# mcu.net
KiCad netlist of a schematic drawn in Altium Designer
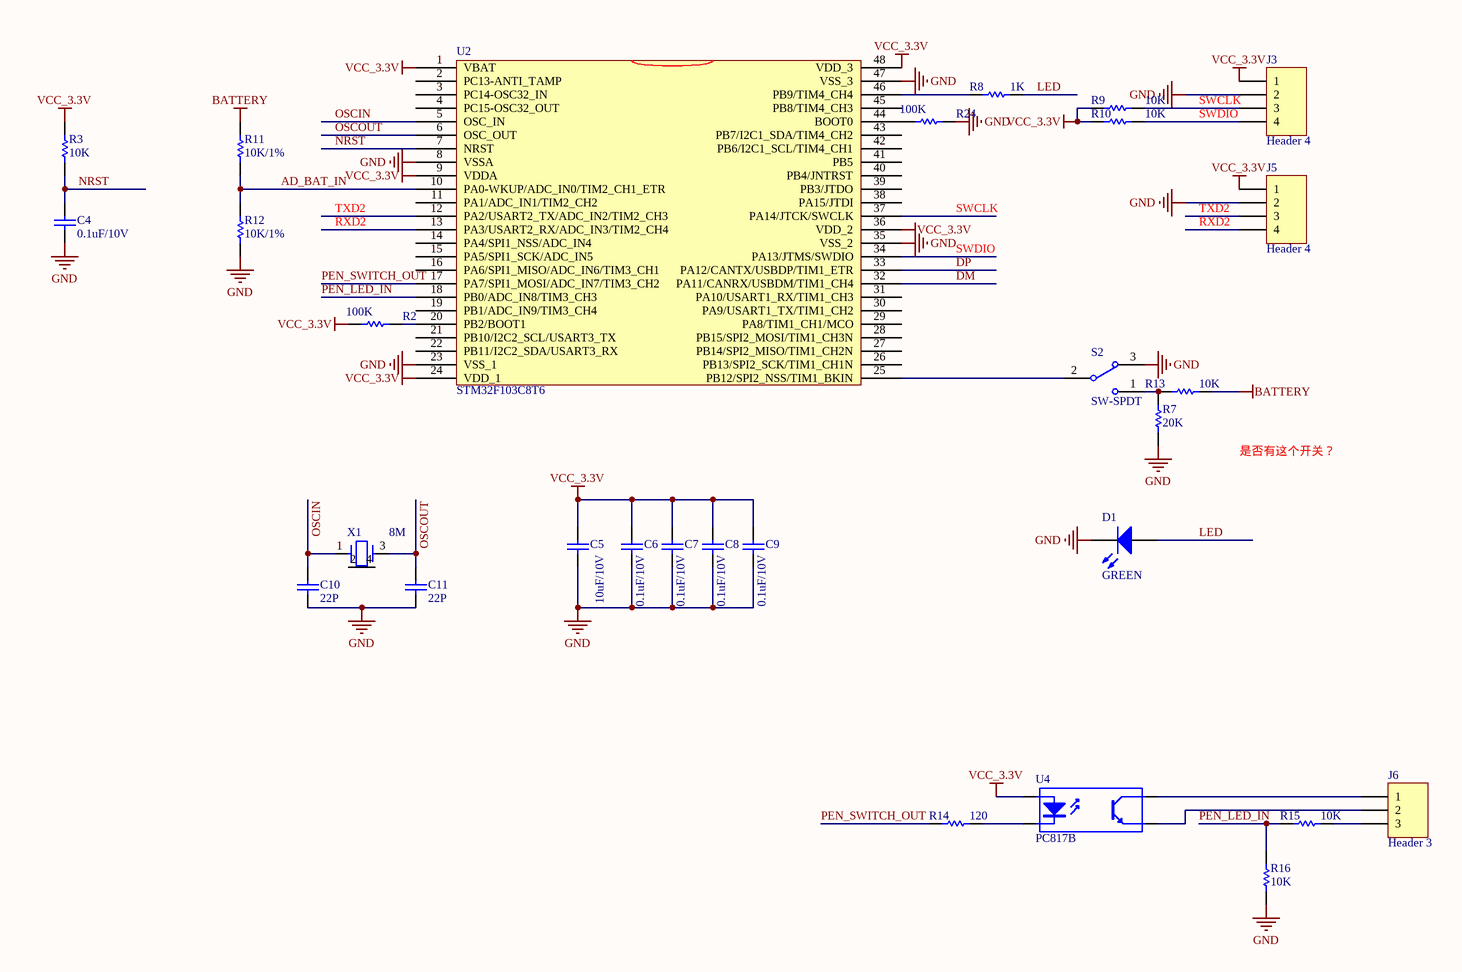
[diagram p0: mcu.SchDoc]

(export (version "E")
  (design (tool "Eeschema 10.0.6"))
  (components
    (comp (ref "C4")
      (value "0.1uF/10V")
      (footprint "0402C")
      (description "Capacitor")
      (fields (field (name "PUBLISHER") "Altium Limited"))
      (libsource (lib "Miscellaneous Devices") (part "Cap"))
    )
    (comp (ref "C5")
      (value "10uF/10V")
      (footprint "0603C")
      (description "Capacitor")
      (fields (field (name "PUBLISHER") "Altium Limited"))
      (libsource (lib "Miscellaneous Devices") (part "Cap"))
    )
    (comp (ref "C6")
      (value "0.1uF/10V")
      (footprint "0402C")
      (description "Capacitor")
      (fields (field (name "PUBLISHER") "Altium Limited"))
      (libsource (lib "Miscellaneous Devices") (part "Cap"))
    )
    (comp (ref "C7")
      (value "0.1uF/10V")
      (footprint "0402C")
      (description "Capacitor")
      (fields (field (name "PUBLISHER") "Altium Limited"))
      (libsource (lib "Miscellaneous Devices") (part "Cap"))
    )
    (comp (ref "C8")
      (value "0.1uF/10V")
      (footprint "0402C")
      (description "Capacitor")
      (fields (field (name "PUBLISHER") "Altium Limited"))
      (libsource (lib "Miscellaneous Devices") (part "Cap"))
    )
    (comp (ref "C9")
      (value "0.1uF/10V")
      (footprint "0402C")
      (description "Capacitor")
      (fields (field (name "PUBLISHER") "Altium Limited"))
      (libsource (lib "Miscellaneous Devices") (part "Cap"))
    )
    (comp (ref "C10")
      (value "22P")
      (footprint "0402C")
      (description "Capacitor")
      (fields (field (name "PUBLISHER") "Altium Limited"))
      (libsource (lib "Miscellaneous Devices") (part "Cap"))
    )
    (comp (ref "C11")
      (value "22P")
      (footprint "0402C")
      (description "Capacitor")
      (fields (field (name "PUBLISHER") "Altium Limited"))
      (libsource (lib "Miscellaneous Devices") (part "Cap"))
    )
    (comp (ref "D1")
      (value "~")
      (footprint "0603LED")
      (description "Typical INFRARED GaAs LED")
      (fields (field (name "PUBLISHER") "GREEN"))
      (libsource (lib "Miscellaneous Devices") (part "LED0"))
    )
    (comp (ref "J3")
      (value "Header 4")
      (footprint "HDR1X4")
      (description "Header, 4-Pin")
      (fields (field (name "PUBLISHER") "Altium Limited"))
      (libsource (lib "Miscellaneous Connectors") (part "Header 4"))
    )
    (comp (ref "J5")
      (value "Header 4")
      (footprint "HDR1X4")
      (description "Header, 4-Pin")
      (fields (field (name "PUBLISHER") "Altium Limited"))
      (libsource (lib "Miscellaneous Connectors") (part "Header 4"))
    )
    (comp (ref "J6")
      (value "Header 3")
      (footprint "HDR1X3")
      (description "Header, 3-Pin")
      (fields (field (name "PUBLISHER") "Altium Limited"))
      (libsource (lib "Miscellaneous Connectors") (part "Header 3"))
    )
    (comp (ref "R2")
      (value "100K")
      (footprint "0402R")
      (description "Resistor")
      (fields (field (name "PUBLISHER") "Altium Limited"))
      (libsource (lib "Miscellaneous Devices") (part "Res1"))
    )
    (comp (ref "R3")
      (value "10K")
      (footprint "0402R")
      (description "Semiconductor Resistor")
      (fields (field (name "PUBLISHER") "Altium Limited"))
      (libsource (lib "Miscellaneous Devices") (part "Res Semi"))
    )
    (comp (ref "R7")
      (value "20K")
      (footprint "0402R")
      (description "Semiconductor Resistor")
      (fields (field (name "PUBLISHER") "Altium Limited"))
      (libsource (lib "Miscellaneous Devices") (part "Res Semi"))
    )
    (comp (ref "R8")
      (value "1K")
      (footprint "0402R")
      (description "Semiconductor Resistor")
      (fields (field (name "PUBLISHER") "Altium Limited"))
      (libsource (lib "Miscellaneous Devices") (part "Res Semi"))
    )
    (comp (ref "R9")
      (value "10K")
      (footprint "0402R")
      (description "Semiconductor Resistor")
      (fields (field (name "PUBLISHER") "Altium Limited"))
      (libsource (lib "Miscellaneous Devices") (part "Res Semi"))
    )
    (comp (ref "R10")
      (value "10K")
      (footprint "0402R")
      (description "Semiconductor Resistor")
      (fields (field (name "PUBLISHER") "Altium Limited"))
      (libsource (lib "Miscellaneous Devices") (part "Res Semi"))
    )
    (comp (ref "R11")
      (value "10K/1%")
      (footprint "0402R")
      (description "Semiconductor Resistor")
      (fields (field (name "PUBLISHER") "Altium Limited"))
      (libsource (lib "Miscellaneous Devices") (part "Res Semi"))
    )
    (comp (ref "R12")
      (value "10K/1%")
      (footprint "0402R")
      (description "Semiconductor Resistor")
      (fields (field (name "PUBLISHER") "Altium Limited"))
      (libsource (lib "Miscellaneous Devices") (part "Res Semi"))
    )
    (comp (ref "R13")
      (value "10K")
      (footprint "0402R")
      (description "Semiconductor Resistor")
      (fields (field (name "PUBLISHER") "Altium Limited"))
      (libsource (lib "Miscellaneous Devices") (part "Res Semi"))
    )
    (comp (ref "R14")
      (value "120")
      (footprint "0402R")
      (description "Semiconductor Resistor")
      (fields (field (name "PUBLISHER") "Altium Limited"))
      (libsource (lib "Miscellaneous Devices") (part "Res Semi"))
    )
    (comp (ref "R15")
      (value "10K")
      (footprint "0402R")
      (description "Semiconductor Resistor")
      (fields (field (name "PUBLISHER") "Altium Limited"))
      (libsource (lib "Miscellaneous Devices") (part "Res Semi"))
    )
    (comp (ref "R16")
      (value "10K")
      (footprint "0402R")
      (description "Semiconductor Resistor")
      (fields (field (name "PUBLISHER") "Altium Limited"))
      (libsource (lib "Miscellaneous Devices") (part "Res Semi"))
    )
    (comp (ref "R24")
      (value "100K")
      (footprint "0402R")
      (description "Resistor")
      (fields (field (name "PUBLISHER") "Altium Limited"))
      (libsource (lib "Miscellaneous Devices") (part "Res1"))
    )
    (comp (ref "S2")
      (value "SW-SPDT")
      (description "SPDT Subminiature Toggle Switch, Right Angle Mounting, Vertical Actuation")
      (fields (field (name "PUBLISHER") "Altium Limited"))
      (libsource (lib "Miscellaneous Devices") (part "SW-SPDT"))
    )
    (comp (ref "U2")
      (value "STM32F103C8T6")
      (footprint "TQFP-48")
      (libsource (lib "stm32") (part "STM32F103C6"))
    )
    (comp (ref "U4")
      (value "PC817B")
      (footprint "DIP-4")
      (description "4-Pin Phototransistor Optocoupler")
      (fields (field (name "PUBLISHER") "Altium Limited"))
      (libsource (lib "Miscellaneous Devices") (part "Optoisolator1"))
    )
    (comp (ref "X1")
      (value "8M")
      (footprint "XTAL4TN_3225")
      (libsource (lib "Schlib_20110825") (part "CRYSTAL-4"))
    )
  )
  (nets
    (net (code "1") (name "/AD_BAT_IN") (class "Default")
      (node (ref "R11") (pin "2") (pinfunction "2_2") (pintype "passive"))
      (node (ref "R12") (pin "1") (pinfunction "1_1") (pintype "passive"))
      (node (ref "U2") (pin "10") (pinfunction "PA0-WKUP/ADC_IN0/TIM2_CH1_ETR_10") (pintype "passive"))
    )
    (net (code "2") (name "/DM") (class "Default")
      (node (ref "U2") (pin "32") (pinfunction "PA11/CANRX/USBDM/TIM1_CH4_32") (pintype "passive"))
    )
    (net (code "3") (name "/DP") (class "Default")
      (node (ref "U2") (pin "33") (pinfunction "PA12/CANTX/USBDP/TIM1_ETR_33") (pintype "passive"))
    )
    (net (code "4") (name "/LED") (class "Default")
      (node (ref "D1") (pin "1") (pinfunction "A_1") (pintype "passive"))
      (node (ref "R8") (pin "2") (pinfunction "2_2") (pintype "passive"))
    )
    (net (code "5") (name "/NRST") (class "Default")
      (node (ref "C4") (pin "2") (pinfunction "2_2") (pintype "passive"))
      (node (ref "R3") (pin "2") (pinfunction "2_2") (pintype "passive"))
      (node (ref "U2") (pin "7") (pinfunction "NRST_7") (pintype "passive"))
    )
    (net (code "6") (name "/OSCIN") (class "Default")
      (node (ref "C10") (pin "2") (pinfunction "2_2") (pintype "passive"))
      (node (ref "U2") (pin "5") (pinfunction "OSC_IN_5") (pintype "passive"))
      (node (ref "X1") (pin "1") (pinfunction "X1_1") (pintype "passive"))
    )
    (net (code "7") (name "/OSCOUT") (class "Default")
      (node (ref "C11") (pin "2") (pinfunction "2_2") (pintype "passive"))
      (node (ref "U2") (pin "6") (pinfunction "OSC_OUT_6") (pintype "passive"))
      (node (ref "X1") (pin "3") (pinfunction "X2_3") (pintype "passive"))
    )
    (net (code "8") (name "/PEN_LED_IN") (class "Default")
      (node (ref "R15") (pin "1") (pinfunction "1_1") (pintype "passive"))
      (node (ref "R16") (pin "2") (pinfunction "2_2") (pintype "passive"))
      (node (ref "U2") (pin "18") (pinfunction "PB0/ADC_IN8/TIM3_CH3_18") (pintype "passive"))
    )
    (net (code "9") (name "/PEN_SWITCH_OUT") (class "Default")
      (node (ref "R14") (pin "1") (pinfunction "1_1") (pintype "passive"))
      (node (ref "U2") (pin "17") (pinfunction "PA7/SPI1_MOSI/ADC_IN7/TIM3_CH2_17") (pintype "passive"))
    )
    (net (code "10") (name "/RXD2") (class "Default")
      (node (ref "J5") (pin "4") (pinfunction "4_4") (pintype "passive"))
      (node (ref "U2") (pin "13") (pinfunction "PA3/USART2_RX/ADC_IN3/TIM2_CH4_13") (pintype "passive"))
    )
    (net (code "11") (name "/SWCLK") (class "Default")
      (node (ref "J3") (pin "3") (pinfunction "3_3") (pintype "passive"))
      (node (ref "R9") (pin "2") (pinfunction "2_2") (pintype "passive"))
      (node (ref "U2") (pin "37") (pinfunction "PA14/JTCK/SWCLK_37") (pintype "passive"))
    )
    (net (code "12") (name "/SWDIO") (class "Default")
      (node (ref "J3") (pin "4") (pinfunction "4_4") (pintype "passive"))
      (node (ref "R10") (pin "2") (pinfunction "2_2") (pintype "passive"))
      (node (ref "U2") (pin "34") (pinfunction "PA13/JTMS/SWDIO_34") (pintype "passive"))
    )
    (net (code "13") (name "/TXD2") (class "Default")
      (node (ref "J5") (pin "3") (pinfunction "3_3") (pintype "passive"))
      (node (ref "U2") (pin "12") (pinfunction "PA2/USART2_TX/ADC_IN2/TIM2_CH3_12") (pintype "passive"))
    )
    (net (code "14") (name "BATTERY") (class "Default")
      (node (ref "R11") (pin "1") (pinfunction "1_1") (pintype "passive"))
      (node (ref "R13") (pin "1") (pinfunction "1_1") (pintype "passive"))
    )
    (net (code "15") (name "GND") (class "Default")
      (node (ref "C10") (pin "1") (pinfunction "1_1") (pintype "passive"))
      (node (ref "C11") (pin "1") (pinfunction "1_1") (pintype "passive"))
      (node (ref "C4") (pin "1") (pinfunction "1_1") (pintype "passive"))
      (node (ref "C5") (pin "1") (pinfunction "1_1") (pintype "passive"))
      (node (ref "C6") (pin "1") (pinfunction "1_1") (pintype "passive"))
      (node (ref "C7") (pin "1") (pinfunction "1_1") (pintype "passive"))
      (node (ref "C8") (pin "1") (pinfunction "1_1") (pintype "passive"))
      (node (ref "C9") (pin "1") (pinfunction "1_1") (pintype "passive"))
      (node (ref "D1") (pin "2") (pinfunction "K_2") (pintype "passive"))
      (node (ref "J3") (pin "2") (pinfunction "2_2") (pintype "passive"))
      (node (ref "J5") (pin "2") (pinfunction "2_2") (pintype "passive"))
      (node (ref "R12") (pin "2") (pinfunction "2_2") (pintype "passive"))
      (node (ref "R16") (pin "1") (pinfunction "1_1") (pintype "passive"))
      (node (ref "R24") (pin "1") (pinfunction "1_1") (pintype "passive"))
      (node (ref "R7") (pin "2") (pinfunction "2_2") (pintype "passive"))
      (node (ref "S2") (pin "3") (pinfunction "3_3") (pintype "passive"))
      (node (ref "U2") (pin "23") (pinfunction "VSS_1_23") (pintype "passive"))
      (node (ref "U2") (pin "35") (pinfunction "VSS_2_35") (pintype "passive"))
      (node (ref "U2") (pin "47") (pinfunction "VSS_3_47") (pintype "passive"))
      (node (ref "U2") (pin "8") (pinfunction "VSSA_8") (pintype "passive"))
    )
    (net (code "16") (name "Net-(J6-Pad3)") (class "Default")
      (node (ref "J6") (pin "3") (pinfunction "3_3") (pintype "passive"))
      (node (ref "R15") (pin "2") (pinfunction "2_2") (pintype "passive"))
    )
    (net (code "17") (name "Net-(R13-Pad2)") (class "Default")
      (node (ref "R13") (pin "2") (pinfunction "2_2") (pintype "passive"))
      (node (ref "R7") (pin "1") (pinfunction "1_1") (pintype "passive"))
      (node (ref "S2") (pin "1") (pinfunction "1_1") (pintype "passive"))
    )
    (net (code "18") (name "Net-(U2-BOOT0)") (class "Default")
      (node (ref "R24") (pin "2") (pinfunction "2_2") (pintype "passive"))
      (node (ref "U2") (pin "44") (pinfunction "BOOT0_44") (pintype "passive"))
    )
    (net (code "19") (name "Net-(U2-PB2{slash}BOOT1)") (class "Default")
      (node (ref "R2") (pin "1") (pinfunction "1_1") (pintype "passive"))
      (node (ref "U2") (pin "20") (pinfunction "PB2/BOOT1_20") (pintype "passive"))
    )
    (net (code "20") (name "Net-(U2-PB9{slash}TIM4_CH4)") (class "Default")
      (node (ref "R8") (pin "1") (pinfunction "1_1") (pintype "passive"))
      (node (ref "U2") (pin "46") (pinfunction "PB9/TIM4_CH4_46") (pintype "passive"))
    )
    (net (code "21") (name "Net-(U2-PB12{slash}SPI2_NSS{slash}TIM1_BKIN)") (class "Default")
      (node (ref "S2") (pin "2") (pinfunction "2_2") (pintype "passive"))
      (node (ref "U2") (pin "25") (pinfunction "PB12/SPI2_NSS/TIM1_BKIN_25") (pintype "passive"))
    )
    (net (code "22") (name "Net-(U4-C)") (class "Default")
      (node (ref "J6") (pin "1") (pinfunction "1_1") (pintype "passive"))
      (node (ref "U4") (pin "4") (pinfunction "C_4") (pintype "passive"))
    )
    (net (code "23") (name "Net-(U4-E)") (class "Default")
      (node (ref "J6") (pin "2") (pinfunction "2_2") (pintype "passive"))
      (node (ref "U4") (pin "3") (pinfunction "E_3") (pintype "passive"))
    )
    (net (code "24") (name "Net-(U4-K)") (class "Default")
      (node (ref "R14") (pin "2") (pinfunction "2_2") (pintype "passive"))
      (node (ref "U4") (pin "2") (pinfunction "K_2") (pintype "passive"))
    )
    (net (code "25") (name "VCC_3.3V") (class "Default")
      (node (ref "C5") (pin "2") (pinfunction "2_2") (pintype "passive"))
      (node (ref "C6") (pin "2") (pinfunction "2_2") (pintype "passive"))
      (node (ref "C7") (pin "2") (pinfunction "2_2") (pintype "passive"))
      (node (ref "C8") (pin "2") (pinfunction "2_2") (pintype "passive"))
      (node (ref "C9") (pin "2") (pinfunction "2_2") (pintype "passive"))
      (node (ref "J3") (pin "1") (pinfunction "1_1") (pintype "passive"))
      (node (ref "J5") (pin "1") (pinfunction "1_1") (pintype "passive"))
      (node (ref "R10") (pin "1") (pinfunction "1_1") (pintype "passive"))
      (node (ref "R2") (pin "2") (pinfunction "2_2") (pintype "passive"))
      (node (ref "R3") (pin "1") (pinfunction "1_1") (pintype "passive"))
      (node (ref "R9") (pin "1") (pinfunction "1_1") (pintype "passive"))
      (node (ref "U2") (pin "1") (pinfunction "VBAT_1") (pintype "passive"))
      (node (ref "U2") (pin "24") (pinfunction "VDD_1_24") (pintype "passive"))
      (node (ref "U2") (pin "36") (pinfunction "VDD_2_36") (pintype "passive"))
      (node (ref "U2") (pin "48") (pinfunction "VDD_3_48") (pintype "passive"))
      (node (ref "U2") (pin "9") (pinfunction "VDDA_9") (pintype "passive"))
      (node (ref "U4") (pin "1") (pinfunction "A_1") (pintype "passive"))
    )
    (net (code "26") (name "unconnected-(U2-PA1{slash}ADC_IN1{slash}TIM2_CH2-Pad11)") (class "Default")
      (node (ref "U2") (pin "11") (pinfunction "PA1/ADC_IN1/TIM2_CH2_11") (pintype "passive"))
    )
    (net (code "27") (name "unconnected-(U2-PA4{slash}SPI1_NSS{slash}ADC_IN4-Pad14)") (class "Default")
      (node (ref "U2") (pin "14") (pinfunction "PA4/SPI1_NSS/ADC_IN4_14") (pintype "passive"))
    )
    (net (code "28") (name "unconnected-(U2-PA5{slash}SPI1_SCK{slash}ADC_IN5-Pad15)") (class "Default")
      (node (ref "U2") (pin "15") (pinfunction "PA5/SPI1_SCK/ADC_IN5_15") (pintype "passive"))
    )
    (net (code "29") (name "unconnected-(U2-PA6{slash}SPI1_MISO{slash}ADC_IN6{slash}TIM3_CH1-Pad16)") (class "Default")
      (node (ref "U2") (pin "16") (pinfunction "PA6/SPI1_MISO/ADC_IN6/TIM3_CH1_16") (pintype "passive"))
    )
    (net (code "30") (name "unconnected-(U2-PA8{slash}TIM1_CH1{slash}MCO-Pad29)") (class "Default")
      (node (ref "U2") (pin "29") (pinfunction "PA8/TIM1_CH1/MCO_29") (pintype "passive"))
    )
    (net (code "31") (name "unconnected-(U2-PA9{slash}USART1_TX{slash}TIM1_CH2-Pad30)") (class "Default")
      (node (ref "U2") (pin "30") (pinfunction "PA9/USART1_TX/TIM1_CH2_30") (pintype "passive"))
    )
    (net (code "32") (name "unconnected-(U2-PA10{slash}USART1_RX{slash}TIM1_CH3-Pad31)") (class "Default")
      (node (ref "U2") (pin "31") (pinfunction "PA10/USART1_RX/TIM1_CH3_31") (pintype "passive"))
    )
    (net (code "33") (name "unconnected-(U2-PA15{slash}JTDI-Pad38)") (class "Default")
      (node (ref "U2") (pin "38") (pinfunction "PA15/JTDI_38") (pintype "passive"))
    )
    (net (code "34") (name "unconnected-(U2-PB1{slash}ADC_IN9{slash}TIM3_CH4-Pad19)") (class "Default")
      (node (ref "U2") (pin "19") (pinfunction "PB1/ADC_IN9/TIM3_CH4_19") (pintype "passive"))
    )
    (net (code "35") (name "unconnected-(U2-PB3{slash}JTDO-Pad39)") (class "Default")
      (node (ref "U2") (pin "39") (pinfunction "PB3/JTDO_39") (pintype "passive"))
    )
    (net (code "36") (name "unconnected-(U2-PB4{slash}JNTRST-Pad40)") (class "Default")
      (node (ref "U2") (pin "40") (pinfunction "PB4/JNTRST_40") (pintype "passive"))
    )
    (net (code "37") (name "unconnected-(U2-PB5-Pad41)") (class "Default")
      (node (ref "U2") (pin "41") (pinfunction "PB5_41") (pintype "passive"))
    )
    (net (code "38") (name "unconnected-(U2-PB6{slash}I2C1_SCL{slash}TIM4_CH1-Pad42)") (class "Default")
      (node (ref "U2") (pin "42") (pinfunction "PB6/I2C1_SCL/TIM4_CH1_42") (pintype "passive"))
    )
    (net (code "39") (name "unconnected-(U2-PB7{slash}I2C1_SDA{slash}TIM4_CH2-Pad43)") (class "Default")
      (node (ref "U2") (pin "43") (pinfunction "PB7/I2C1_SDA/TIM4_CH2_43") (pintype "passive"))
    )
    (net (code "40") (name "unconnected-(U2-PB8{slash}TIM4_CH3-Pad45)") (class "Default")
      (node (ref "U2") (pin "45") (pinfunction "PB8/TIM4_CH3_45") (pintype "passive"))
    )
    (net (code "41") (name "unconnected-(U2-PB10{slash}I2C2_SCL{slash}USART3_TX-Pad21)") (class "Default")
      (node (ref "U2") (pin "21") (pinfunction "PB10/I2C2_SCL/USART3_TX_21") (pintype "passive"))
    )
    (net (code "42") (name "unconnected-(U2-PB11{slash}I2C2_SDA{slash}USART3_RX-Pad22)") (class "Default")
      (node (ref "U2") (pin "22") (pinfunction "PB11/I2C2_SDA/USART3_RX_22") (pintype "passive"))
    )
    (net (code "43") (name "unconnected-(U2-PB13{slash}SPI2_SCK{slash}TIM1_CH1N-Pad26)") (class "Default")
      (node (ref "U2") (pin "26") (pinfunction "PB13/SPI2_SCK/TIM1_CH1N_26") (pintype "passive"))
    )
    (net (code "44") (name "unconnected-(U2-PB14{slash}SPI2_MISO{slash}TIM1_CH2N-Pad27)") (class "Default")
      (node (ref "U2") (pin "27") (pinfunction "PB14/SPI2_MISO/TIM1_CH2N_27") (pintype "passive"))
    )
    (net (code "45") (name "unconnected-(U2-PB15{slash}SPI2_MOSI{slash}TIM1_CH3N-Pad28)") (class "Default")
      (node (ref "U2") (pin "28") (pinfunction "PB15/SPI2_MOSI/TIM1_CH3N_28") (pintype "passive"))
    )
    (net (code "46") (name "unconnected-(U2-PC13-ANTI_TAMP-Pad2)") (class "Default")
      (node (ref "U2") (pin "2") (pinfunction "PC13-ANTI_TAMP_2") (pintype "passive"))
    )
    (net (code "47") (name "unconnected-(U2-PC14-OSC32_IN-Pad3)") (class "Default")
      (node (ref "U2") (pin "3") (pinfunction "PC14-OSC32_IN_3") (pintype "passive"))
    )
    (net (code "48") (name "unconnected-(U2-PC15-OSC32_OUT-Pad4)") (class "Default")
      (node (ref "U2") (pin "4") (pinfunction "PC15-OSC32_OUT_4") (pintype "passive"))
    )
    (net (code "49") (name "unconnected-(X1-GND-Pad2)") (class "Default")
      (node (ref "X1") (pin "2") (pinfunction "GND_2") (pintype "passive"))
    )
    (net (code "50") (name "unconnected-(X1-GND-Pad4)") (class "Default")
      (node (ref "X1") (pin "4") (pinfunction "GND_4") (pintype "passive"))
    )
  )
)
